# FDL-2X_CTRL.net
KiCad netlist of a schematic drawn in EAGLE
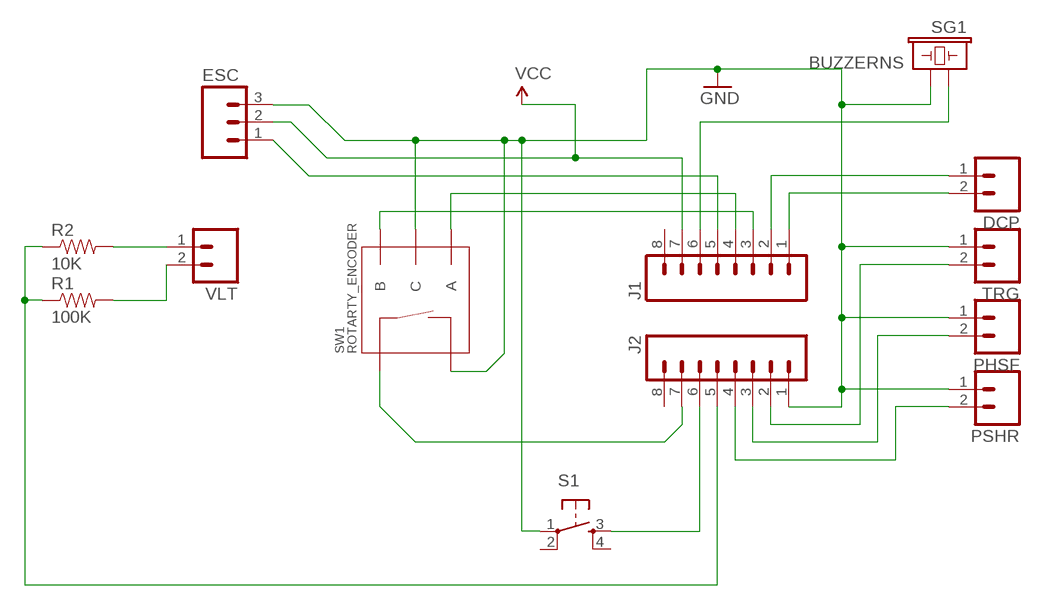
[diagram p0: schematic, sheet 1]

(export (version "E")
  (design (tool "Eeschema 10.0.6"))
  (components
    (comp (ref "DCP")
      (value "M02PTH")
      (footprint "eagle-import:1X02")
      (libsource (lib "eagle-import") (part "M02PTH"))
    )
    (comp (ref "ESC")
      (value "M03PTH")
      (footprint "eagle-import:1X03")
      (libsource (lib "eagle-import") (part "M03PTH"))
    )
    (comp (ref "J1")
      (value "M08SILK_FEMALE_PTH")
      (footprint "eagle-import:1X08")
      (libsource (lib "eagle-import") (part "M08SILK_FEMALE_PTH"))
    )
    (comp (ref "J2")
      (value "M08SILK_FEMALE_PTH")
      (footprint "eagle-import:1X08")
      (libsource (lib "eagle-import") (part "M08SILK_FEMALE_PTH"))
    )
    (comp (ref "PHSF")
      (value "M02PTH")
      (footprint "eagle-import:1X02")
      (libsource (lib "eagle-import") (part "M02PTH"))
    )
    (comp (ref "PSHR")
      (value "M02PTH")
      (footprint "eagle-import:1X02")
      (libsource (lib "eagle-import") (part "M02PTH"))
    )
    (comp (ref "R1")
      (value "100K")
      (footprint "eagle-import:AXIAL-0.3")
      (libsource (lib "eagle-import") (part "RESISTORAXIAL-0.3"))
    )
    (comp (ref "R2")
      (value "10K")
      (footprint "eagle-import:AXIAL-0.3")
      (libsource (lib "eagle-import") (part "RESISTORAXIAL-0.3"))
    )
    (comp (ref "S1")
      (value "TAC_SWITCHPTH")
      (footprint "eagle-import:TACTILE-PTH")
      (libsource (lib "eagle-import") (part "TAC_SWITCHPTH"))
    )
    (comp (ref "SG1")
      (value "BUZZERNS")
      (footprint "eagle-import:BUZZER-12MM-NS")
      (libsource (lib "eagle-import") (part "BUZZERNS"))
    )
    (comp (ref "SW1")
      (value "ROTARTY_ENCODER")
      (footprint "eagle-import:ROTARY_ENC_PLAIN")
      (libsource (lib "eagle-import") (part "ROTARTY_ENCODER"))
    )
    (comp (ref "TRG")
      (value "M02PTH")
      (footprint "eagle-import:1X02")
      (libsource (lib "eagle-import") (part "M02PTH"))
    )
    (comp (ref "VLT")
      (value "M02PTH")
      (footprint "eagle-import:1X02")
      (libsource (lib "eagle-import") (part "M02PTH"))
    )
  )
  (nets
    (net (code "1") (name "GND") (class "Default")
      (node (ref "ESC") (pin "3") (pinfunction "3_3") (pintype "passive"))
      (node (ref "J2") (pin "1") (pinfunction "1_1") (pintype "passive"))
      (node (ref "PHSF") (pin "1") (pinfunction "1_1") (pintype "passive"))
      (node (ref "PSHR") (pin "1") (pinfunction "1_1") (pintype "passive"))
      (node (ref "S1") (pin "1") (pinfunction "1_1") (pintype "passive"))
      (node (ref "SG1") (pin "-") (pinfunction "2_-") (pintype "passive"))
      (node (ref "SW1") (pin "C") (pinfunction "C_C") (pintype "bidirectional"))
      (node (ref "SW1") (pin "SW-") (pinfunction "SW-_SW-") (pintype "bidirectional"))
      (node (ref "TRG") (pin "1") (pinfunction "1_1") (pintype "passive"))
    )
    (net (code "2") (name "Net-(DCP-Pad1)") (class "Default")
      (node (ref "DCP") (pin "1") (pinfunction "1_1") (pintype "passive"))
      (node (ref "J1") (pin "2") (pinfunction "2_2") (pintype "passive"))
    )
    (net (code "3") (name "Net-(DCP-Pad2)") (class "Default")
      (node (ref "DCP") (pin "2") (pinfunction "2_2") (pintype "passive"))
      (node (ref "J1") (pin "1") (pinfunction "1_1") (pintype "passive"))
    )
    (net (code "4") (name "Net-(ESC-Pad1)") (class "Default")
      (node (ref "ESC") (pin "1") (pinfunction "1_1") (pintype "passive"))
      (node (ref "J1") (pin "5") (pinfunction "5_5") (pintype "passive"))
    )
    (net (code "5") (name "Net-(J1-Pad3)") (class "Default")
      (node (ref "J1") (pin "3") (pinfunction "3_3") (pintype "passive"))
      (node (ref "SW1") (pin "B") (pinfunction "B_B") (pintype "bidirectional"))
    )
    (net (code "6") (name "Net-(J1-Pad4)") (class "Default")
      (node (ref "J1") (pin "4") (pinfunction "4_4") (pintype "passive"))
      (node (ref "SW1") (pin "A") (pinfunction "A_A") (pintype "bidirectional"))
    )
    (net (code "7") (name "Net-(J2-Pad2)") (class "Default")
      (node (ref "J2") (pin "2") (pinfunction "2_2") (pintype "passive"))
      (node (ref "TRG") (pin "2") (pinfunction "2_2") (pintype "passive"))
    )
    (net (code "8") (name "Net-(J2-Pad3)") (class "Default")
      (node (ref "J2") (pin "3") (pinfunction "3_3") (pintype "passive"))
      (node (ref "PHSF") (pin "2") (pinfunction "2_2") (pintype "passive"))
    )
    (net (code "9") (name "Net-(J2-Pad4)") (class "Default")
      (node (ref "J2") (pin "4") (pinfunction "4_4") (pintype "passive"))
      (node (ref "PSHR") (pin "2") (pinfunction "2_2") (pintype "passive"))
    )
    (net (code "10") (name "Net-(J2-Pad6)") (class "Default")
      (node (ref "J2") (pin "6") (pinfunction "6_6") (pintype "passive"))
      (node (ref "S1") (pin "3") (pinfunction "3_3") (pintype "passive"))
    )
    (net (code "11") (name "Net-(J2-Pad7)") (class "Default")
      (node (ref "J2") (pin "7") (pinfunction "7_7") (pintype "passive"))
      (node (ref "SW1") (pin "SW+") (pinfunction "SW+_SW+") (pintype "bidirectional"))
    )
    (net (code "12") (name "Net-(R1-1)") (class "Default")
      (node (ref "J2") (pin "5") (pinfunction "5_5") (pintype "passive"))
      (node (ref "R1") (pin "P$1") (pinfunction "1_P$1") (pintype "passive"))
      (node (ref "R2") (pin "P$1") (pinfunction "1_P$1") (pintype "passive"))
    )
    (net (code "13") (name "Net-(R1-2)") (class "Default")
      (node (ref "R1") (pin "P$2") (pinfunction "2_P$2") (pintype "passive"))
      (node (ref "VLT") (pin "2") (pinfunction "2_2") (pintype "passive"))
    )
    (net (code "14") (name "Net-(R2-2)") (class "Default")
      (node (ref "R2") (pin "P$2") (pinfunction "2_P$2") (pintype "passive"))
      (node (ref "VLT") (pin "1") (pinfunction "1_1") (pintype "passive"))
    )
    (net (code "15") (name "Net-(SG1-1)") (class "Default")
      (node (ref "J1") (pin "6") (pinfunction "6_6") (pintype "passive"))
      (node (ref "SG1") (pin "+") (pinfunction "1_+") (pintype "passive"))
    )
    (net (code "16") (name "VCC") (class "Default")
      (node (ref "ESC") (pin "2") (pinfunction "2_2") (pintype "passive"))
      (node (ref "J1") (pin "7") (pinfunction "7_7") (pintype "passive"))
    )
    (net (code "17") (name "unconnected-(J1-Pad8)") (class "Default")
      (node (ref "J1") (pin "8") (pinfunction "8_8") (pintype "passive"))
    )
    (net (code "18") (name "unconnected-(J2-Pad8)") (class "Default")
      (node (ref "J2") (pin "8") (pinfunction "8_8") (pintype "passive"))
    )
    (net (code "19") (name "unconnected-(S1-Pad2)") (class "Default")
      (node (ref "S1") (pin "2") (pinfunction "2_2") (pintype "passive"))
    )
    (net (code "20") (name "unconnected-(S1-Pad4)") (class "Default")
      (node (ref "S1") (pin "4") (pinfunction "4_4") (pintype "passive"))
    )
  )
)
